# button_control_esp32.net
KiCad netlist of a schematic drawn in EAGLE
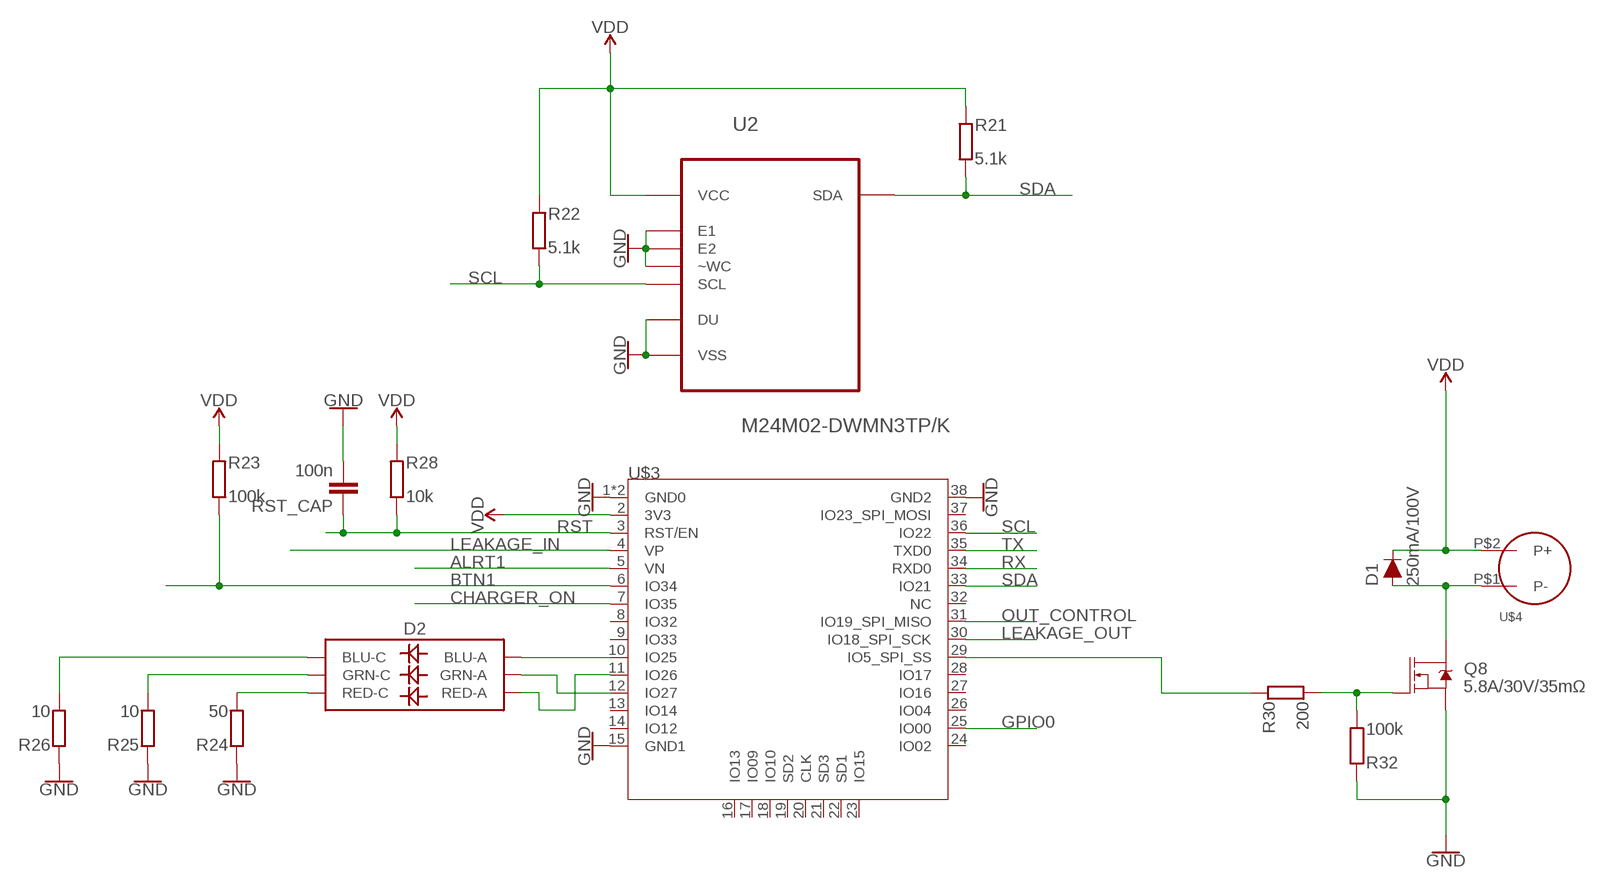
[diagram p0: schematic, sheet 1]
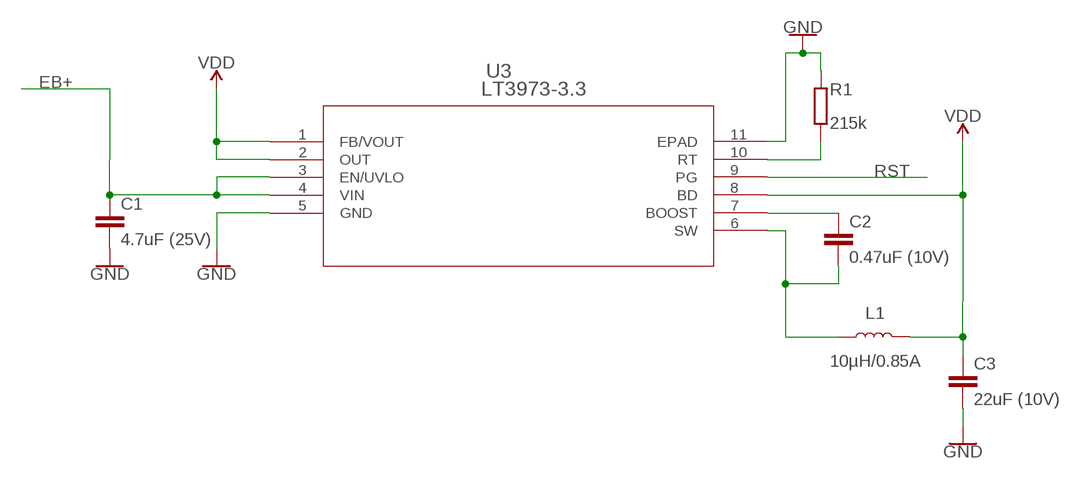
[diagram p1: schematic, sheet 2]
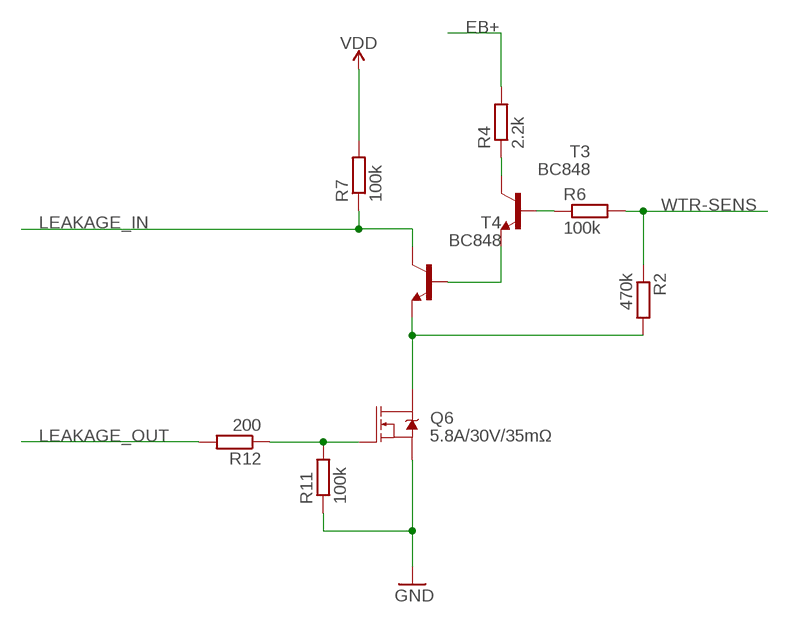
[diagram p2: schematic, sheet 3]
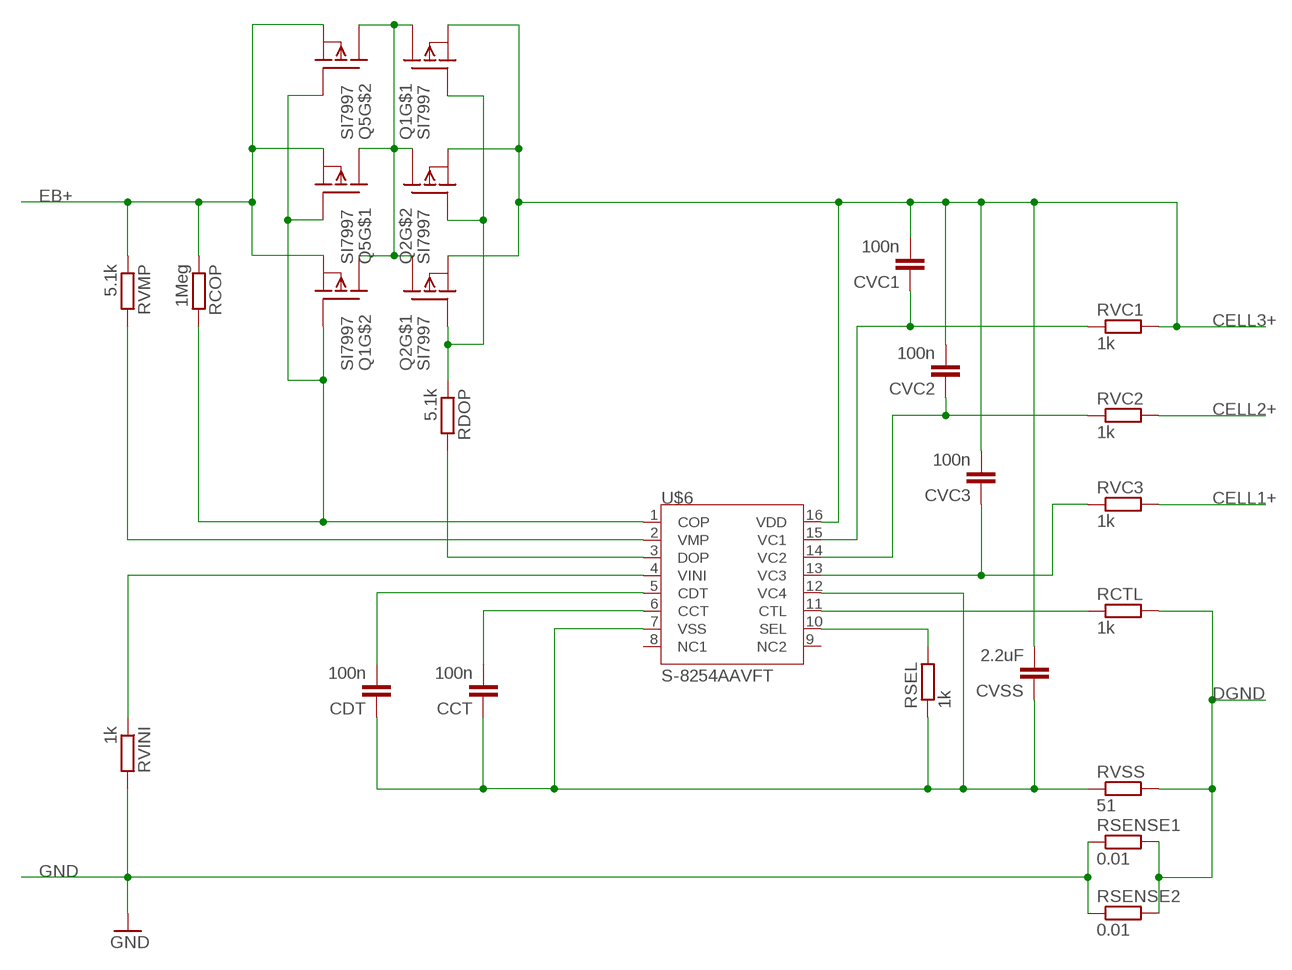
[diagram p3: schematic, sheet 4]
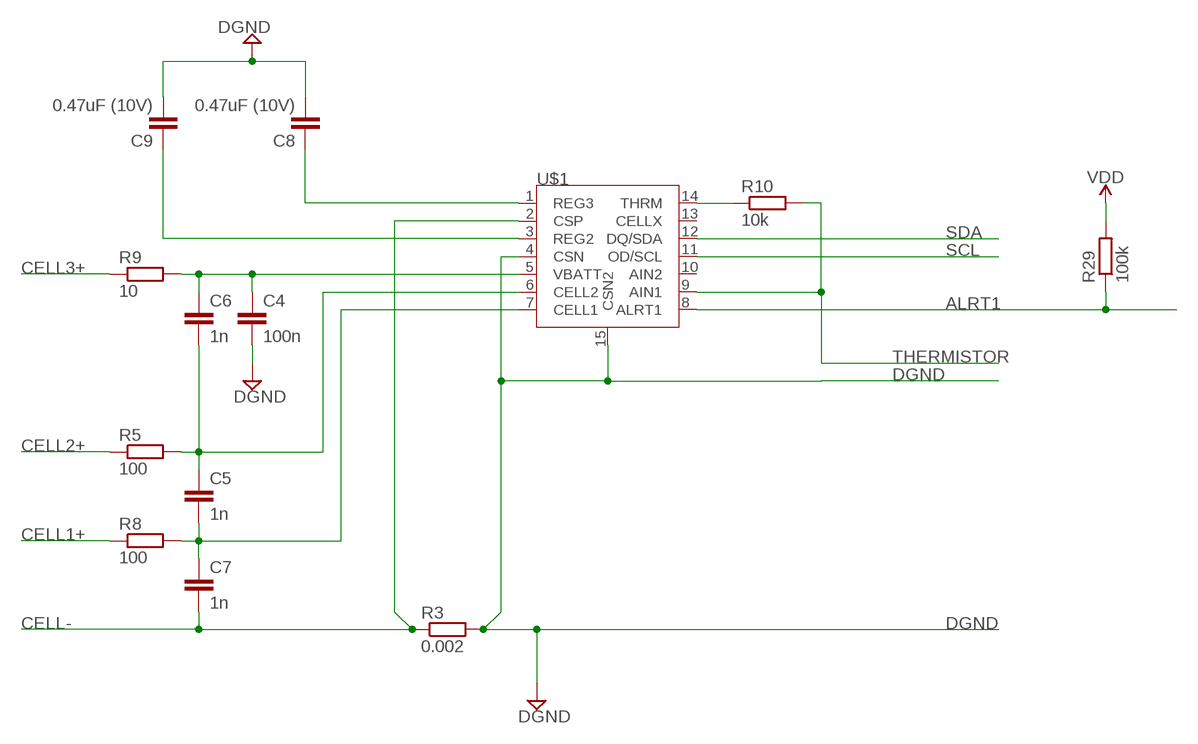
[diagram p4: schematic, sheet 5]
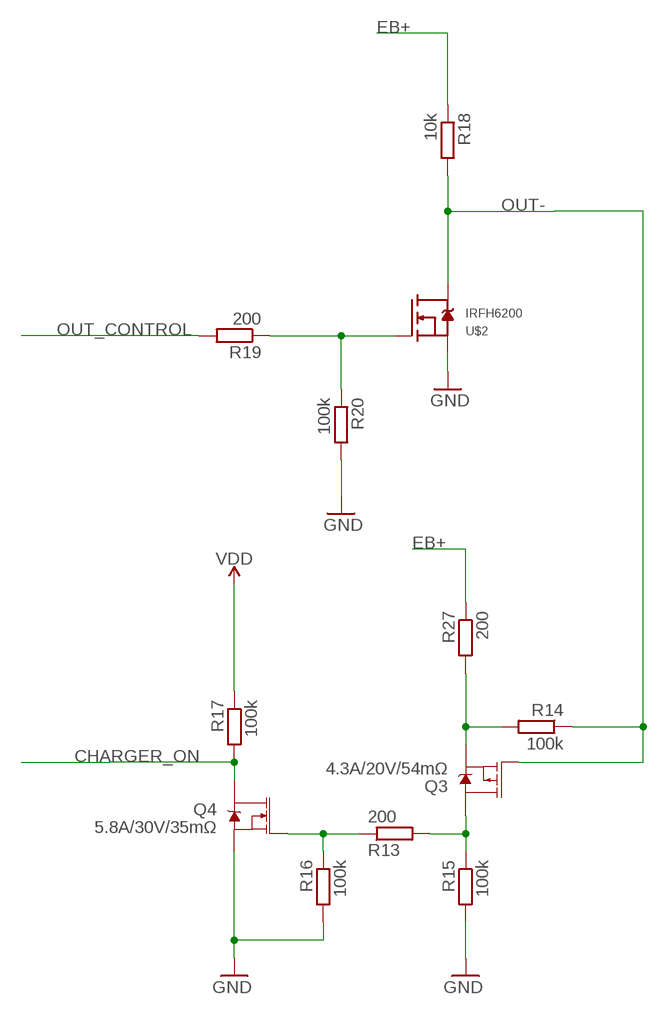
[diagram p5: schematic, sheet 6]
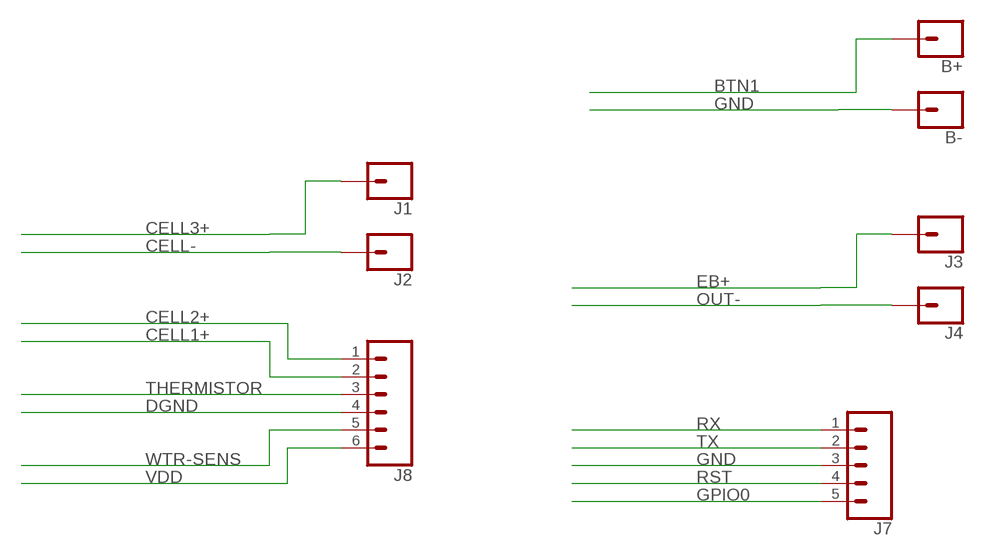
[diagram p6: schematic, sheet 7]

(export (version "E")
  (design (tool "Eeschema 10.0.6"))
  (components
    (comp (ref "CCT")
      (value "100n")
      (footprint "eagle-import:C0603")
      (libsource (lib "eagle-import") (part "C-EUC0603"))
    )
    (comp (ref "CDT")
      (value "100n")
      (footprint "eagle-import:C0603")
      (libsource (lib "eagle-import") (part "C-EUC0603"))
    )
    (comp (ref "CVC1")
      (value "100n")
      (footprint "eagle-import:C0603")
      (libsource (lib "eagle-import") (part "C-EUC0603"))
    )
    (comp (ref "CVC2")
      (value "100n")
      (footprint "eagle-import:C0603")
      (libsource (lib "eagle-import") (part "C-EUC0603"))
    )
    (comp (ref "CVC3")
      (value "100n")
      (footprint "eagle-import:C0603")
      (libsource (lib "eagle-import") (part "C-EUC0603"))
    )
    (comp (ref "CVSS")
      (value "2.2uF")
      (footprint "eagle-import:C0805")
      (libsource (lib "eagle-import") (part "C-EUC0805"))
    )
    (comp (ref "Q1")
      (value "SI7997")
      (footprint "eagle-import:POWERPAK")
      (libsource (lib "eagle-import") (part "SI7997"))
    )
    (comp (ref "Q2")
      (value "SI7997")
      (footprint "eagle-import:POWERPAK")
      (libsource (lib "eagle-import") (part "SI7997"))
    )
    (comp (ref "Q5")
      (value "SI7997")
      (footprint "eagle-import:POWERPAK")
      (libsource (lib "eagle-import") (part "SI7997"))
    )
    (comp (ref "RCOP")
      (value "1Meg")
      (footprint "eagle-import:R0603")
      (libsource (lib "eagle-import") (part "resistor_348_R-EU_R0603"))
    )
    (comp (ref "RCTL")
      (value "1k")
      (footprint "eagle-import:R0603")
      (libsource (lib "eagle-import") (part "resistor_348_R-EU_R0603"))
    )
    (comp (ref "RDOP")
      (value "5.1k")
      (footprint "eagle-import:R0603")
      (libsource (lib "eagle-import") (part "resistor_348_R-EU_R0603"))
    )
    (comp (ref "RSEL")
      (value "1k")
      (footprint "eagle-import:R0603")
      (libsource (lib "eagle-import") (part "resistor_348_R-EU_R0603"))
    )
    (comp (ref "RSENSE1")
      (value "0.01")
      (footprint "eagle-import:R2512")
      (libsource (lib "eagle-import") (part "resistor_348_R-EU_R2512"))
    )
    (comp (ref "RSENSE2")
      (value "0.01")
      (footprint "eagle-import:R2512")
      (libsource (lib "eagle-import") (part "resistor_348_R-EU_R2512"))
    )
    (comp (ref "RVC1")
      (value "1k")
      (footprint "eagle-import:R0603")
      (libsource (lib "eagle-import") (part "resistor_348_R-EU_R0603"))
    )
    (comp (ref "RVC2")
      (value "1k")
      (footprint "eagle-import:R0603")
      (libsource (lib "eagle-import") (part "resistor_348_R-EU_R0603"))
    )
    (comp (ref "RVC3")
      (value "1k")
      (footprint "eagle-import:R0603")
      (libsource (lib "eagle-import") (part "resistor_348_R-EU_R0603"))
    )
    (comp (ref "RVINI")
      (value "1k")
      (footprint "eagle-import:R0603")
      (libsource (lib "eagle-import") (part "resistor_348_R-EU_R0603"))
    )
    (comp (ref "RVMP")
      (value "5.1k")
      (footprint "eagle-import:R0603")
      (libsource (lib "eagle-import") (part "resistor_348_R-EU_R0603"))
    )
    (comp (ref "RVSS")
      (value "51")
      (footprint "eagle-import:R0603")
      (libsource (lib "eagle-import") (part "resistor_348_R-EU_R0603"))
    )
    (comp (ref "U$6")
      (value "S-8254AAVFT")
      (footprint "eagle-import:TSSOP-16")
      (libsource (lib "eagle-import") (part "S-8254A"))
    )
    (comp (ref "C4")
      (value "100n")
      (footprint "eagle-import:C0603")
      (libsource (lib "eagle-import") (part "C-EUC0603"))
    )
    (comp (ref "C5")
      (value "1n")
      (footprint "eagle-import:C0603")
      (libsource (lib "eagle-import") (part "C-EUC0603"))
    )
    (comp (ref "C6")
      (value "1n")
      (footprint "eagle-import:C0603")
      (libsource (lib "eagle-import") (part "C-EUC0603"))
    )
    (comp (ref "C7")
      (value "1n")
      (footprint "eagle-import:C0603")
      (libsource (lib "eagle-import") (part "C-EUC0603"))
    )
    (comp (ref "C8")
      (value "0.47uF (10V)")
      (footprint "eagle-import:C0603K")
      (libsource (lib "eagle-import") (part "C-EUC0603K"))
    )
    (comp (ref "C9")
      (value "0.47uF (10V)")
      (footprint "eagle-import:C0603K")
      (libsource (lib "eagle-import") (part "C-EUC0603K"))
    )
    (comp (ref "R3")
      (value "0.002")
      (footprint "eagle-import:R2512")
      (libsource (lib "eagle-import") (part "resistor_348_R-EU_R2512"))
    )
    (comp (ref "R5")
      (value "100")
      (footprint "eagle-import:R0805")
      (libsource (lib "eagle-import") (part "resistor_348_R-EU_R0805"))
    )
    (comp (ref "R8")
      (value "100")
      (footprint "eagle-import:R0805")
      (libsource (lib "eagle-import") (part "resistor_348_R-EU_R0805"))
    )
    (comp (ref "R9")
      (value "10")
      (footprint "eagle-import:R0603")
      (libsource (lib "eagle-import") (part "resistor_348_R-EU_R0603"))
    )
    (comp (ref "R10")
      (value "10k")
      (footprint "eagle-import:R0603")
      (libsource (lib "eagle-import") (part "resistor_348_R-EU_R0603"))
    )
    (comp (ref "R29")
      (value "100k")
      (footprint "eagle-import:R0603")
      (libsource (lib "eagle-import") (part "resistor_348_R-EU_R0603"))
    )
    (comp (ref "U$1")
      (value "MAX17205G")
      (footprint "eagle-import:SON40P300X300X80-15N230X170")
      (libsource (lib "eagle-import") (part "MAX17205G"))
    )
    (comp (ref "Q3")
      (value "4.3A/20V/54mΩ")
      (footprint "eagle-import:SOT23-3")
      (libsource (lib "eagle-import") (part "MOSFET_PCH-IRLML2244"))
    )
    (comp (ref "Q4")
      (value "5.8A/30V/35mΩ")
      (footprint "eagle-import:SOT23-3")
      (libsource (lib "eagle-import") (part "MOSFET-NCH-AO3404A"))
    )
    (comp (ref "R13")
      (value "200")
      (footprint "eagle-import:R0603")
      (libsource (lib "eagle-import") (part "R-EU_R0603"))
    )
    (comp (ref "R14")
      (value "100k")
      (footprint "eagle-import:R0603")
      (libsource (lib "eagle-import") (part "R-EU_R0603"))
    )
    (comp (ref "R15")
      (value "100k")
      (footprint "eagle-import:R0603")
      (libsource (lib "eagle-import") (part "R-EU_R0603"))
    )
    (comp (ref "R16")
      (value "100k")
      (footprint "eagle-import:R0603")
      (libsource (lib "eagle-import") (part "R-EU_R0603"))
    )
    (comp (ref "R17")
      (value "100k")
      (footprint "eagle-import:R0603")
      (libsource (lib "eagle-import") (part "R-EU_R0603"))
    )
    (comp (ref "R18")
      (value "10k")
      (footprint "eagle-import:R0603")
      (libsource (lib "eagle-import") (part "R-EU_R0603"))
    )
    (comp (ref "R19")
      (value "200")
      (footprint "eagle-import:R0603")
      (libsource (lib "eagle-import") (part "R-EU_R0603"))
    )
    (comp (ref "R20")
      (value "100k")
      (footprint "eagle-import:R0603")
      (libsource (lib "eagle-import") (part "R-EU_R0603"))
    )
    (comp (ref "R27")
      (value "200")
      (footprint "eagle-import:R0603")
      (libsource (lib "eagle-import") (part "R-EU_R0603"))
    )
    (comp (ref "U$2")
      (value "IRFH6200")
      (footprint "eagle-import:PQFN")
      (libsource (lib "eagle-import") (part "IRFH6200"))
    )
    (comp (ref "C1")
      (value "4.7uF (25V)")
      (footprint "eagle-import:C1206")
      (libsource (lib "eagle-import") (part "C-EUC1206"))
    )
    (comp (ref "C2")
      (value "0.47uF (10V)")
      (footprint "eagle-import:C0603K")
      (libsource (lib "eagle-import") (part "C-EUC0603K"))
    )
    (comp (ref "C3")
      (value "22uF (10V)")
      (footprint "eagle-import:C1206")
      (libsource (lib "eagle-import") (part "C-EUC1206"))
    )
    (comp (ref "L1")
      (value "10µH/0.85A")
      (footprint "eagle-import:INDUCTOR_4.7UH")
      (libsource (lib "eagle-import") (part "INDUCTOR-CDRH-4.7UH"))
    )
    (comp (ref "R1")
      (value "215k")
      (footprint "eagle-import:R0603")
      (libsource (lib "eagle-import") (part "resistor_348_R-EU_R0603"))
    )
    (comp (ref "U3")
      (value "LT3973-3.3")
      (footprint "eagle-import:DFN-10_DD")
      (fields
        (field (name "DIGI-KEY_PART_NUMBER") "LT3973IDD#PBF-ND")
        (field (name "MF") "Linear Technology")
        (field (name "MP") "LT3973IDD#PBF")
      )
      (libsource (lib "eagle-import") (part "LT3973IDDPBF"))
    )
    (comp (ref "B+")
      (value "CONN_01")
      (footprint "eagle-import:1X01")
      (libsource (lib "eagle-import") (part "CONN_01"))
    )
    (comp (ref "B-")
      (value "CONN_01")
      (footprint "eagle-import:1X01")
      (libsource (lib "eagle-import") (part "CONN_01"))
    )
    (comp (ref "J1")
      (value "CONN_01PTH_2MM")
      (footprint "eagle-import:1X01_2MM")
      (libsource (lib "eagle-import") (part "CONN_01PTH_2MM"))
    )
    (comp (ref "J2")
      (value "CONN_01PTH_2MM")
      (footprint "eagle-import:1X01_2MM")
      (libsource (lib "eagle-import") (part "CONN_01PTH_2MM"))
    )
    (comp (ref "J3")
      (value "CONN_01PTH_2MM")
      (footprint "eagle-import:1X01_2MM")
      (libsource (lib "eagle-import") (part "CONN_01PTH_2MM"))
    )
    (comp (ref "J4")
      (value "CONN_01PTH_2MM")
      (footprint "eagle-import:1X01_2MM")
      (libsource (lib "eagle-import") (part "CONN_01PTH_2MM"))
    )
    (comp (ref "J7")
      (value "CONN_051.27MM")
      (footprint "eagle-import:1X05_1.27MM")
      (libsource (lib "eagle-import") (part "CONN_051.27MM"))
    )
    (comp (ref "J8")
      (value "CONN_061.27MM")
      (footprint "eagle-import:1X06_1.27MM")
      (libsource (lib "eagle-import") (part "CONN_061.27MM"))
    )
    (comp (ref "D1")
      (value "250mA/100V")
      (footprint "eagle-import:SOD-323")
      (libsource (lib "eagle-import") (part "DIODE-BAS16J"))
    )
    (comp (ref "D2")
      (value "LED-RGBNO_IC")
      (footprint "eagle-import:LED-TRICOLOR-5050")
      (libsource (lib "eagle-import") (part "LED-RGBNO_IC"))
    )
    (comp (ref "Q8")
      (value "5.8A/30V/35mΩ")
      (footprint "eagle-import:SOT23-3")
      (libsource (lib "eagle-import") (part "MOSFET-NCH-AO3404A"))
    )
    (comp (ref "R21")
      (value "5.1k")
      (footprint "eagle-import:R0603")
      (libsource (lib "eagle-import") (part "resistor_348_R-EU_R0603"))
    )
    (comp (ref "R22")
      (value "5.1k")
      (footprint "eagle-import:R0603")
      (libsource (lib "eagle-import") (part "resistor_348_R-EU_R0603"))
    )
    (comp (ref "R23")
      (value "100k")
      (footprint "eagle-import:R0603")
      (libsource (lib "eagle-import") (part "resistor_348_R-EU_R0603"))
    )
    (comp (ref "R24")
      (value "50")
      (footprint "eagle-import:R0603")
      (libsource (lib "eagle-import") (part "resistor_348_R-EU_R0603"))
    )
    (comp (ref "R25")
      (value "10")
      (footprint "eagle-import:R0603")
      (libsource (lib "eagle-import") (part "resistor_348_R-EU_R0603"))
    )
    (comp (ref "R26")
      (value "10")
      (footprint "eagle-import:R0603")
      (libsource (lib "eagle-import") (part "resistor_348_R-EU_R0603"))
    )
    (comp (ref "R28")
      (value "10k")
      (footprint "eagle-import:R0603")
      (libsource (lib "eagle-import") (part "resistor_348_R-EU_R0603"))
    )
    (comp (ref "R30")
      (value "200")
      (footprint "eagle-import:R0603")
      (libsource (lib "eagle-import") (part "resistor_348_R-EU_R0603"))
    )
    (comp (ref "R32")
      (value "100k")
      (footprint "eagle-import:R0603")
      (libsource (lib "eagle-import") (part "resistor_348_R-EU_R0603"))
    )
    (comp (ref "RST_CAP")
      (value "100n")
      (footprint "eagle-import:C0603")
      (libsource (lib "eagle-import") (part "C-EUC0603"))
    )
    (comp (ref "U$3")
      (value "ESP32")
      (footprint "eagle-import:TTGO_ESP32")
      (libsource (lib "eagle-import") (part "ESP32"))
    )
    (comp (ref "U$4")
      (value "VIBRO")
      (footprint "eagle-import:VIBRO")
      (libsource (lib "eagle-import") (part "VIBRO"))
    )
    (comp (ref "U2")
      (value "M24M02-DWMN3TP/K")
      (footprint "eagle-import:SOIC127P600X175-8N")
      (fields (field (name "DIGI-KEY_PART_NUMBER") "497-16238-1-ND") (field (name "MF") "STMicroelectronics"))
      (libsource (lib "eagle-import") (part "M24M02-DWMN3TP/K"))
    )
    (comp (ref "Q6")
      (value "5.8A/30V/35mΩ")
      (footprint "eagle-import:SOT23-3")
      (libsource (lib "eagle-import") (part "MOSFET-NCH-AO3404A"))
    )
    (comp (ref "R2")
      (value "470k")
      (footprint "eagle-import:R0603")
      (libsource (lib "eagle-import") (part "R-EU_R0603"))
    )
    (comp (ref "R4")
      (value "2.2k")
      (footprint "eagle-import:R0603")
      (libsource (lib "eagle-import") (part "R-EU_R0603"))
    )
    (comp (ref "R6")
      (value "100k")
      (footprint "eagle-import:R0603")
      (libsource (lib "eagle-import") (part "R-EU_R0603"))
    )
    (comp (ref "R7")
      (value "100k")
      (footprint "eagle-import:R0603")
      (libsource (lib "eagle-import") (part "R-EU_R0603"))
    )
    (comp (ref "R11")
      (value "100k")
      (footprint "eagle-import:R0603")
      (libsource (lib "eagle-import") (part "R-EU_R0603"))
    )
    (comp (ref "R12")
      (value "200")
      (footprint "eagle-import:R0603")
      (libsource (lib "eagle-import") (part "R-EU_R0603"))
    )
    (comp (ref "T3")
      (value "BC848")
      (footprint "eagle-import:SOT23")
      (libsource (lib "eagle-import") (part "BC848"))
    )
    (comp (ref "T4")
      (value "BC848")
      (footprint "eagle-import:SOT23")
      (fields (field (name "SPICEPREFIX") "Q"))
      (libsource (lib "eagle-import") (part "BC848"))
    )
  )
  (nets
    (net (code "1") (name "ALRT1") (class "Default")
      (node (ref "R29") (pin "1") (pinfunction "1_1") (pintype "passive"))
      (node (ref "U$1") (pin "8") (pinfunction "ALRT1_8") (pintype "bidirectional"))
      (node (ref "U$3") (pin "5") (pinfunction "VN_5") (pintype "bidirectional"))
    )
    (net (code "2") (name "BTN1") (class "Default")
      (node (ref "B+") (pin "1") (pinfunction "1_1") (pintype "passive"))
      (node (ref "R23") (pin "1") (pinfunction "1_1") (pintype "passive"))
      (node (ref "U$3") (pin "6") (pinfunction "IO34_6") (pintype "bidirectional"))
    )
    (net (code "3") (name "CELL-") (class "Default")
      (node (ref "C7") (pin "2") (pinfunction "2_2") (pintype "passive"))
      (node (ref "J2") (pin "1") (pinfunction "1_1") (pintype "passive"))
      (node (ref "R3") (pin "1") (pinfunction "1_1") (pintype "passive"))
      (node (ref "U$1") (pin "2") (pinfunction "CSP_2") (pintype "bidirectional"))
    )
    (net (code "4") (name "CELL1+") (class "Default")
      (node (ref "J8") (pin "2") (pinfunction "2_2") (pintype "passive"))
      (node (ref "R8") (pin "1") (pinfunction "1_1") (pintype "passive"))
      (node (ref "RVC3") (pin "2") (pinfunction "2_2") (pintype "passive"))
    )
    (net (code "5") (name "CELL2+") (class "Default")
      (node (ref "J8") (pin "1") (pinfunction "1_1") (pintype "passive"))
      (node (ref "R5") (pin "1") (pinfunction "1_1") (pintype "passive"))
      (node (ref "RVC2") (pin "2") (pinfunction "2_2") (pintype "passive"))
    )
    (net (code "6") (name "CELL3+") (class "Default")
      (node (ref "CVC1") (pin "2") (pinfunction "2_2") (pintype "passive"))
      (node (ref "CVC2") (pin "2") (pinfunction "2_2") (pintype "passive"))
      (node (ref "CVC3") (pin "2") (pinfunction "2_2") (pintype "passive"))
      (node (ref "CVSS") (pin "2") (pinfunction "2_2") (pintype "passive"))
      (node (ref "J1") (pin "1") (pinfunction "1_1") (pintype "passive"))
      (node (ref "Q1") (pin "1") (pinfunction "S_1") (pintype "passive"))
      (node (ref "Q2") (pin "1") (pinfunction "S_1") (pintype "passive"))
      (node (ref "Q2") (pin "3") (pinfunction "S_3") (pintype "passive"))
      (node (ref "R9") (pin "1") (pinfunction "1_1") (pintype "passive"))
      (node (ref "RVC1") (pin "2") (pinfunction "2_2") (pintype "passive"))
      (node (ref "U$6") (pin "16") (pinfunction "VDD_16") (pintype "bidirectional"))
    )
    (net (code "7") (name "CHARGER_ON") (class "Default")
      (node (ref "Q4") (pin "3") (pinfunction "D_3") (pintype "bidirectional"))
      (node (ref "R17") (pin "2") (pinfunction "2_2") (pintype "passive"))
      (node (ref "U$3") (pin "7") (pinfunction "IO35_7") (pintype "bidirectional"))
    )
    (net (code "8") (name "DGND") (class "Default")
      (node (ref "C4") (pin "2") (pinfunction "2_2") (pintype "passive"))
      (node (ref "C8") (pin "2") (pinfunction "2_2") (pintype "passive"))
      (node (ref "C9") (pin "2") (pinfunction "2_2") (pintype "passive"))
      (node (ref "J8") (pin "4") (pinfunction "4_4") (pintype "passive"))
      (node (ref "R3") (pin "2") (pinfunction "2_2") (pintype "passive"))
      (node (ref "RCTL") (pin "2") (pinfunction "2_2") (pintype "passive"))
      (node (ref "RSENSE1") (pin "2") (pinfunction "2_2") (pintype "passive"))
      (node (ref "RSENSE2") (pin "2") (pinfunction "2_2") (pintype "passive"))
      (node (ref "RVSS") (pin "2") (pinfunction "2_2") (pintype "passive"))
      (node (ref "U$1") (pin "15") (pinfunction "CSN2_15") (pintype "bidirectional"))
      (node (ref "U$1") (pin "4") (pinfunction "CSN_4") (pintype "bidirectional"))
    )
    (net (code "9") (name "EB+") (class "Default")
      (node (ref "C1") (pin "1") (pinfunction "1_1") (pintype "passive"))
      (node (ref "J3") (pin "1") (pinfunction "1_1") (pintype "passive"))
      (node (ref "Q1") (pin "3") (pinfunction "S_3") (pintype "passive"))
      (node (ref "Q5") (pin "1") (pinfunction "S_1") (pintype "passive"))
      (node (ref "Q5") (pin "3") (pinfunction "S_3") (pintype "passive"))
      (node (ref "R18") (pin "1") (pinfunction "1_1") (pintype "passive"))
      (node (ref "R27") (pin "1") (pinfunction "1_1") (pintype "passive"))
      (node (ref "R4") (pin "2") (pinfunction "2_2") (pintype "passive"))
      (node (ref "RCOP") (pin "1") (pinfunction "1_1") (pintype "passive"))
      (node (ref "RVMP") (pin "1") (pinfunction "1_1") (pintype "passive"))
      (node (ref "U3") (pin "3") (pinfunction "EN/UVLO_3") (pintype "bidirectional"))
      (node (ref "U3") (pin "4") (pinfunction "VIN_4") (pintype "input"))
    )
    (net (code "10") (name "GND") (class "Default")
      (node (ref "B-") (pin "1") (pinfunction "1_1") (pintype "passive"))
      (node (ref "C1") (pin "2") (pinfunction "2_2") (pintype "passive"))
      (node (ref "C3") (pin "2") (pinfunction "2_2") (pintype "passive"))
      (node (ref "J7") (pin "3") (pinfunction "3_3") (pintype "passive"))
      (node (ref "Q4") (pin "2") (pinfunction "S_2") (pintype "bidirectional"))
      (node (ref "Q6") (pin "2") (pinfunction "S_2") (pintype "bidirectional"))
      (node (ref "Q8") (pin "2") (pinfunction "S_2") (pintype "bidirectional"))
      (node (ref "R1") (pin "2") (pinfunction "2_2") (pintype "passive"))
      (node (ref "R11") (pin "1") (pinfunction "1_1") (pintype "passive"))
      (node (ref "R15") (pin "2") (pinfunction "2_2") (pintype "passive"))
      (node (ref "R16") (pin "2") (pinfunction "2_2") (pintype "passive"))
      (node (ref "R20") (pin "2") (pinfunction "2_2") (pintype "passive"))
      (node (ref "R24") (pin "2") (pinfunction "2_2") (pintype "passive"))
      (node (ref "R25") (pin "2") (pinfunction "2_2") (pintype "passive"))
      (node (ref "R26") (pin "2") (pinfunction "2_2") (pintype "passive"))
      (node (ref "R32") (pin "2") (pinfunction "2_2") (pintype "passive"))
      (node (ref "RSENSE1") (pin "1") (pinfunction "1_1") (pintype "passive"))
      (node (ref "RSENSE2") (pin "1") (pinfunction "1_1") (pintype "passive"))
      (node (ref "RST_CAP") (pin "2") (pinfunction "2_2") (pintype "passive"))
      (node (ref "RVINI") (pin "2") (pinfunction "2_2") (pintype "passive"))
      (node (ref "U$2") (pin "1") (pinfunction "S_1") (pintype "power_in"))
      (node (ref "U$2") (pin "2") (pinfunction "S_2") (pintype "power_in"))
      (node (ref "U$2") (pin "3") (pinfunction "S_3") (pintype "power_in"))
      (node (ref "U$3") (pin "1") (pinfunction "GND0_1") (pintype "bidirectional"))
      (node (ref "U$3") (pin "15") (pinfunction "GND1_15") (pintype "bidirectional"))
      (node (ref "U$3") (pin "38") (pinfunction "GND2_38") (pintype "bidirectional"))
      (node (ref "U$3") (pin "P$1") (pinfunction "GND0_P$1") (pintype "bidirectional"))
      (node (ref "U2") (pin "1") (pinfunction "DU_1") (pintype "input"))
      (node (ref "U2") (pin "2") (pinfunction "E1_2") (pintype "input"))
      (node (ref "U2") (pin "3") (pinfunction "E2_3") (pintype "input"))
      (node (ref "U2") (pin "4") (pinfunction "VSS_4") (pintype "power_in"))
      (node (ref "U2") (pin "7") (pinfunction "~{WC}_7") (pintype "input"))
      (node (ref "U3") (pin "11") (pinfunction "EPAD_11") (pintype "passive"))
      (node (ref "U3") (pin "5") (pinfunction "GND_5") (pintype "power_in"))
    )
    (net (code "11") (name "GPIO0") (class "Default")
      (node (ref "J7") (pin "5") (pinfunction "5_5") (pintype "passive"))
      (node (ref "U$3") (pin "25") (pinfunction "IO00_25") (pintype "bidirectional"))
    )
    (net (code "12") (name "LEAKAGE_IN") (class "Default")
      (node (ref "R7") (pin "1") (pinfunction "1_1") (pintype "passive"))
      (node (ref "T4") (pin "3") (pinfunction "C_3") (pintype "passive"))
      (node (ref "U$3") (pin "4") (pinfunction "VP_4") (pintype "bidirectional"))
    )
    (net (code "13") (name "LEAKAGE_OUT") (class "Default")
      (node (ref "R12") (pin "2") (pinfunction "2_2") (pintype "passive"))
      (node (ref "U$3") (pin "30") (pinfunction "IO18_SPI_SCK_30") (pintype "bidirectional"))
    )
    (net (code "14") (name "Net-(D2-BLU-A)") (class "Default")
      (node (ref "D2") (pin "3") (pinfunction "BLU-A_3") (pintype "bidirectional"))
      (node (ref "U$3") (pin "10") (pinfunction "IO25_10") (pintype "bidirectional"))
    )
    (net (code "15") (name "Net-(D2-BLU-C)") (class "Default")
      (node (ref "D2") (pin "4") (pinfunction "BLU-C_4") (pintype "bidirectional"))
      (node (ref "R26") (pin "1") (pinfunction "1_1") (pintype "passive"))
    )
    (net (code "16") (name "Net-(D2-GRN-A)") (class "Default")
      (node (ref "D2") (pin "1") (pinfunction "GRN-A_1") (pintype "bidirectional"))
      (node (ref "U$3") (pin "12") (pinfunction "IO27_12") (pintype "bidirectional"))
    )
    (net (code "17") (name "Net-(D2-GRN-C)") (class "Default")
      (node (ref "D2") (pin "6") (pinfunction "GRN-C_6") (pintype "bidirectional"))
      (node (ref "R25") (pin "1") (pinfunction "1_1") (pintype "passive"))
    )
    (net (code "18") (name "Net-(D2-RED-A)") (class "Default")
      (node (ref "D2") (pin "2") (pinfunction "RED-A_2") (pintype "bidirectional"))
      (node (ref "U$3") (pin "11") (pinfunction "IO26_11") (pintype "bidirectional"))
    )
    (net (code "19") (name "Net-(D2-RED-C)") (class "Default")
      (node (ref "D2") (pin "5") (pinfunction "RED-C_5") (pintype "bidirectional"))
      (node (ref "R24") (pin "1") (pinfunction "1_1") (pintype "passive"))
    )
    (net (code "20") (name "Net-(L1-1)") (class "Default")
      (node (ref "C2") (pin "2") (pinfunction "2_2") (pintype "passive"))
      (node (ref "L1") (pin "P$1") (pinfunction "1_P$1") (pintype "passive"))
      (node (ref "U3") (pin "6") (pinfunction "SW_6") (pintype "output"))
    )
    (net (code "21") (name "Net-(Q1A-D-Pad7)") (class "Default")
      (node (ref "Q1") (pin "5") (pinfunction "D_5") (pintype "passive"))
      (node (ref "Q1") (pin "5_6") (pinfunction "D_5_6") (pintype "passive"))
      (node (ref "Q1") (pin "6") (pinfunction "D_6") (pintype "passive"))
      (node (ref "Q1") (pin "7") (pinfunction "D_7") (pintype "passive"))
      (node (ref "Q1") (pin "7_8") (pinfunction "D_7_8") (pintype "passive"))
      (node (ref "Q1") (pin "8") (pinfunction "D_8") (pintype "passive"))
      (node (ref "Q2") (pin "5") (pinfunction "D_5") (pintype "passive"))
      (node (ref "Q2") (pin "5_6") (pinfunction "D_5_6") (pintype "passive"))
      (node (ref "Q2") (pin "6") (pinfunction "D_6") (pintype "passive"))
      (node (ref "Q2") (pin "7") (pinfunction "D_7") (pintype "passive"))
      (node (ref "Q2") (pin "7_8") (pinfunction "D_7_8") (pintype "passive"))
      (node (ref "Q2") (pin "8") (pinfunction "D_8") (pintype "passive"))
      (node (ref "Q5") (pin "5") (pinfunction "D_5") (pintype "passive"))
      (node (ref "Q5") (pin "5_6") (pinfunction "D_5_6") (pintype "passive"))
      (node (ref "Q5") (pin "6") (pinfunction "D_6") (pintype "passive"))
      (node (ref "Q5") (pin "7") (pinfunction "D_7") (pintype "passive"))
      (node (ref "Q5") (pin "7_8") (pinfunction "D_7_8") (pintype "passive"))
      (node (ref "Q5") (pin "8") (pinfunction "D_8") (pintype "passive"))
    )
    (net (code "22") (name "Net-(Q1A-G)") (class "Default")
      (node (ref "Q1") (pin "2") (pinfunction "G_2") (pintype "passive"))
      (node (ref "Q2") (pin "2") (pinfunction "G_2") (pintype "passive"))
      (node (ref "Q2") (pin "4") (pinfunction "G_4") (pintype "passive"))
      (node (ref "RDOP") (pin "1") (pinfunction "1_1") (pintype "passive"))
    )
    (net (code "23") (name "Net-(Q1B-G)") (class "Default")
      (node (ref "Q1") (pin "4") (pinfunction "G_4") (pintype "passive"))
      (node (ref "Q5") (pin "2") (pinfunction "G_2") (pintype "passive"))
      (node (ref "Q5") (pin "4") (pinfunction "G_4") (pintype "passive"))
      (node (ref "RCOP") (pin "2") (pinfunction "2_2") (pintype "passive"))
      (node (ref "U$6") (pin "1") (pinfunction "COP_1") (pintype "bidirectional"))
    )
    (net (code "24") (name "Net-(Q3-D)") (class "Default")
      (node (ref "Q3") (pin "3") (pinfunction "D_3") (pintype "bidirectional"))
      (node (ref "R13") (pin "2") (pinfunction "2_2") (pintype "passive"))
      (node (ref "R15") (pin "1") (pinfunction "1_1") (pintype "passive"))
    )
    (net (code "25") (name "Net-(Q3-S)") (class "Default")
      (node (ref "Q3") (pin "2") (pinfunction "S_2") (pintype "bidirectional"))
      (node (ref "R14") (pin "2") (pinfunction "2_2") (pintype "passive"))
      (node (ref "R27") (pin "2") (pinfunction "2_2") (pintype "passive"))
    )
    (net (code "26") (name "Net-(Q4-G)") (class "Default")
      (node (ref "Q4") (pin "1") (pinfunction "G_1") (pintype "bidirectional"))
      (node (ref "R13") (pin "1") (pinfunction "1_1") (pintype "passive"))
      (node (ref "R16") (pin "1") (pinfunction "1_1") (pintype "passive"))
    )
    (net (code "27") (name "Net-(Q6-D)") (class "Default")
      (node (ref "Q6") (pin "3") (pinfunction "D_3") (pintype "bidirectional"))
      (node (ref "R2") (pin "2") (pinfunction "2_2") (pintype "passive"))
      (node (ref "T4") (pin "2") (pinfunction "E_2") (pintype "passive"))
    )
    (net (code "28") (name "Net-(Q6-G)") (class "Default")
      (node (ref "Q6") (pin "1") (pinfunction "G_1") (pintype "bidirectional"))
      (node (ref "R11") (pin "2") (pinfunction "2_2") (pintype "passive"))
      (node (ref "R12") (pin "1") (pinfunction "1_1") (pintype "passive"))
    )
    (net (code "29") (name "Net-(Q8-D)") (class "Default")
      (node (ref "D1") (pin "A") (pinfunction "A_A") (pintype "passive"))
      (node (ref "Q8") (pin "3") (pinfunction "D_3") (pintype "bidirectional"))
      (node (ref "U$4") (pin "P$1") (pinfunction "P-_P$1") (pintype "power_in"))
    )
    (net (code "30") (name "Net-(Q8-G)") (class "Default")
      (node (ref "Q8") (pin "1") (pinfunction "G_1") (pintype "bidirectional"))
      (node (ref "R30") (pin "1") (pinfunction "1_1") (pintype "passive"))
      (node (ref "R32") (pin "1") (pinfunction "1_1") (pintype "passive"))
    )
    (net (code "31") (name "Net-(T3-B)") (class "Default")
      (node (ref "R6") (pin "1") (pinfunction "1_1") (pintype "passive"))
      (node (ref "T3") (pin "1") (pinfunction "B_1") (pintype "passive"))
    )
    (net (code "32") (name "Net-(T3-C)") (class "Default")
      (node (ref "R4") (pin "1") (pinfunction "1_1") (pintype "passive"))
      (node (ref "T3") (pin "3") (pinfunction "C_3") (pintype "passive"))
    )
    (net (code "33") (name "Net-(T3-E)") (class "Default")
      (node (ref "T3") (pin "2") (pinfunction "E_2") (pintype "passive"))
      (node (ref "T4") (pin "1") (pinfunction "B_1") (pintype "passive"))
    )
    (net (code "34") (name "Net-(U$1-CELL1)") (class "Default")
      (node (ref "C5") (pin "2") (pinfunction "2_2") (pintype "passive"))
      (node (ref "C7") (pin "1") (pinfunction "1_1") (pintype "passive"))
      (node (ref "R8") (pin "2") (pinfunction "2_2") (pintype "passive"))
      (node (ref "U$1") (pin "7") (pinfunction "CELL1_7") (pintype "bidirectional"))
    )
    (net (code "35") (name "Net-(U$1-CELL2)") (class "Default")
      (node (ref "C5") (pin "1") (pinfunction "1_1") (pintype "passive"))
      (node (ref "C6") (pin "2") (pinfunction "2_2") (pintype "passive"))
      (node (ref "R5") (pin "2") (pinfunction "2_2") (pintype "passive"))
      (node (ref "U$1") (pin "6") (pinfunction "CELL2_6") (pintype "bidirectional"))
    )
    (net (code "36") (name "Net-(U$1-REG2)") (class "Default")
      (node (ref "C9") (pin "1") (pinfunction "1_1") (pintype "passive"))
      (node (ref "U$1") (pin "3") (pinfunction "REG2_3") (pintype "bidirectional"))
    )
    (net (code "37") (name "Net-(U$1-REG3)") (class "Default")
      (node (ref "C8") (pin "1") (pinfunction "1_1") (pintype "passive"))
      (node (ref "U$1") (pin "1") (pinfunction "REG3_1") (pintype "bidirectional"))
    )
    (net (code "38") (name "Net-(U$1-THRM)") (class "Default")
      (node (ref "R10") (pin "1") (pinfunction "1_1") (pintype "passive"))
      (node (ref "U$1") (pin "14") (pinfunction "THRM_14") (pintype "bidirectional"))
    )
    (net (code "39") (name "Net-(U$1-VBATT)") (class "Default")
      (node (ref "C4") (pin "1") (pinfunction "1_1") (pintype "passive"))
      (node (ref "C6") (pin "1") (pinfunction "1_1") (pintype "passive"))
      (node (ref "R9") (pin "2") (pinfunction "2_2") (pintype "passive"))
      (node (ref "U$1") (pin "5") (pinfunction "VBATT_5") (pintype "bidirectional"))
    )
    (net (code "40") (name "Net-(U$2-G)") (class "Default")
      (node (ref "R19") (pin "1") (pinfunction "1_1") (pintype "passive"))
      (node (ref "R20") (pin "1") (pinfunction "1_1") (pintype "passive"))
      (node (ref "U$2") (pin "4") (pinfunction "G_4") (pintype "bidirectional"))
    )
    (net (code "41") (name "Net-(U$3-IO5_SPI_SS)") (class "Default")
      (node (ref "R30") (pin "2") (pinfunction "2_2") (pintype "passive"))
      (node (ref "U$3") (pin "29") (pinfunction "IO5_SPI_SS_29") (pintype "bidirectional"))
    )
    (net (code "42") (name "Net-(U$6-CCT)") (class "Default")
      (node (ref "CCT") (pin "2") (pinfunction "2_2") (pintype "passive"))
      (node (ref "U$6") (pin "6") (pinfunction "CCT_6") (pintype "bidirectional"))
    )
    (net (code "43") (name "Net-(U$6-CDT)") (class "Default")
      (node (ref "CDT") (pin "2") (pinfunction "2_2") (pintype "passive"))
      (node (ref "U$6") (pin "5") (pinfunction "CDT_5") (pintype "bidirectional"))
    )
    (net (code "44") (name "Net-(U$6-CTL)") (class "Default")
      (node (ref "RCTL") (pin "1") (pinfunction "1_1") (pintype "passive"))
      (node (ref "U$6") (pin "11") (pinfunction "CTL_11") (pintype "bidirectional"))
    )
    (net (code "45") (name "Net-(U$6-DOP)") (class "Default")
      (node (ref "RDOP") (pin "2") (pinfunction "2_2") (pintype "passive"))
      (node (ref "U$6") (pin "3") (pinfunction "DOP_3") (pintype "bidirectional"))
    )
    (net (code "46") (name "Net-(U$6-SEL)") (class "Default")
      (node (ref "RSEL") (pin "2") (pinfunction "2_2") (pintype "passive"))
      (node (ref "U$6") (pin "10") (pinfunction "SEL_10") (pintype "bidirectional"))
    )
    (net (code "47") (name "Net-(U$6-VC1)") (class "Default")
      (node (ref "CVC1") (pin "1") (pinfunction "1_1") (pintype "passive"))
      (node (ref "RVC1") (pin "1") (pinfunction "1_1") (pintype "passive"))
      (node (ref "U$6") (pin "15") (pinfunction "VC1_15") (pintype "bidirectional"))
    )
    (net (code "48") (name "Net-(U$6-VC2)") (class "Default")
      (node (ref "CVC2") (pin "1") (pinfunction "1_1") (pintype "passive"))
      (node (ref "RVC2") (pin "1") (pinfunction "1_1") (pintype "passive"))
      (node (ref "U$6") (pin "14") (pinfunction "VC2_14") (pintype "bidirectional"))
    )
    (net (code "49") (name "Net-(U$6-VC3)") (class "Default")
      (node (ref "CVC3") (pin "1") (pinfunction "1_1") (pintype "passive"))
      (node (ref "RVC3") (pin "1") (pinfunction "1_1") (pintype "passive"))
      (node (ref "U$6") (pin "13") (pinfunction "VC3_13") (pintype "bidirectional"))
    )
    (net (code "50") (name "Net-(U$6-VC4)") (class "Default")
      (node (ref "CCT") (pin "1") (pinfunction "1_1") (pintype "passive"))
      (node (ref "CDT") (pin "1") (pinfunction "1_1") (pintype "passive"))
      (node (ref "CVSS") (pin "1") (pinfunction "1_1") (pintype "passive"))
      (node (ref "RSEL") (pin "1") (pinfunction "1_1") (pintype "passive"))
      (node (ref "RVSS") (pin "1") (pinfunction "1_1") (pintype "passive"))
      (node (ref "U$6") (pin "12") (pinfunction "VC4_12") (pintype "bidirectional"))
      (node (ref "U$6") (pin "7") (pinfunction "VSS_7") (pintype "bidirectional"))
    )
    (net (code "51") (name "Net-(U$6-VINI)") (class "Default")
      (node (ref "RVINI") (pin "1") (pinfunction "1_1") (pintype "passive"))
      (node (ref "U$6") (pin "4") (pinfunction "VINI_4") (pintype "bidirectional"))
    )
    (net (code "52") (name "Net-(U$6-VMP)") (class "Default")
      (node (ref "RVMP") (pin "2") (pinfunction "2_2") (pintype "passive"))
      (node (ref "U$6") (pin "2") (pinfunction "VMP_2") (pintype "bidirectional"))
    )
    (net (code "53") (name "Net-(U3-BOOST)") (class "Default")
      (node (ref "C2") (pin "1") (pinfunction "1_1") (pintype "passive"))
      (node (ref "U3") (pin "7") (pinfunction "BOOST_7") (pintype "input"))
    )
    (net (code "54") (name "Net-(U3-RT)") (class "Default")
      (node (ref "R1") (pin "1") (pinfunction "1_1") (pintype "passive"))
      (node (ref "U3") (pin "10") (pinfunction "RT_10") (pintype "passive"))
    )
    (net (code "55") (name "OUT-") (class "Default")
      (node (ref "J4") (pin "1") (pinfunction "1_1") (pintype "passive"))
      (node (ref "Q3") (pin "1") (pinfunction "G_1") (pintype "bidirectional"))
      (node (ref "R14") (pin "1") (pinfunction "1_1") (pintype "passive"))
      (node (ref "R18") (pin "2") (pinfunction "2_2") (pintype "passive"))
      (node (ref "U$2") (pin "5") (pinfunction "D_5") (pintype "power_in"))
      (node (ref "U$2") (pin "6") (pinfunction "D_6") (pintype "power_in"))
      (node (ref "U$2") (pin "7") (pinfunction "D_7") (pintype "power_in"))
      (node (ref "U$2") (pin "8") (pinfunction "D_8") (pintype "power_in"))
      (node (ref "U$2") (pin "9") (pinfunction "D_9") (pintype "power_in"))
    )
    (net (code "56") (name "OUT_CONTROL") (class "Default")
      (node (ref "R19") (pin "2") (pinfunction "2_2") (pintype "passive"))
      (node (ref "U$3") (pin "31") (pinfunction "IO19_SPI_MISO_31") (pintype "bidirectional"))
    )
    (net (code "57") (name "RST") (class "Default")
      (node (ref "J7") (pin "4") (pinfunction "4_4") (pintype "passive"))
      (node (ref "R28") (pin "1") (pinfunction "1_1") (pintype "passive"))
      (node (ref "RST_CAP") (pin "1") (pinfunction "1_1") (pintype "passive"))
      (node (ref "U$3") (pin "3") (pinfunction "RST/EN_3") (pintype "bidirectional"))
      (node (ref "U3") (pin "9") (pinfunction "PG_9") (pintype "output"))
    )
    (net (code "58") (name "RX") (class "Default")
      (node (ref "J7") (pin "1") (pinfunction "1_1") (pintype "passive"))
      (node (ref "U$3") (pin "34") (pinfunction "RXD0_34") (pintype "bidirectional"))
    )
    (net (code "59") (name "SCL") (class "Default")
      (node (ref "R22") (pin "1") (pinfunction "1_1") (pintype "passive"))
      (node (ref "U$1") (pin "11") (pinfunction "OD/SCL_11") (pintype "bidirectional"))
      (node (ref "U$3") (pin "36") (pinfunction "IO22_36") (pintype "bidirectional"))
      (node (ref "U2") (pin "6") (pinfunction "SCL_6") (pintype "input"))
    )
    (net (code "60") (name "SDA") (class "Default")
      (node (ref "R21") (pin "1") (pinfunction "1_1") (pintype "passive"))
      (node (ref "U$1") (pin "12") (pinfunction "DQ/SDA_12") (pintype "bidirectional"))
      (node (ref "U$3") (pin "33") (pinfunction "IO21_33") (pintype "bidirectional"))
      (node (ref "U2") (pin "5") (pinfunction "SDA_5") (pintype "output"))
    )
    (net (code "61") (name "THERMISTOR") (class "Default")
      (node (ref "J8") (pin "3") (pinfunction "3_3") (pintype "passive"))
      (node (ref "R10") (pin "2") (pinfunction "2_2") (pintype "passive"))
      (node (ref "U$1") (pin "9") (pinfunction "AIN1_9") (pintype "bidirectional"))
    )
    (net (code "62") (name "TX") (class "Default")
      (node (ref "J7") (pin "2") (pinfunction "2_2") (pintype "passive"))
      (node (ref "U$3") (pin "35") (pinfunction "TXD0_35") (pintype "bidirectional"))
    )
    (net (code "63") (name "VDD") (class "Default")
      (node (ref "C3") (pin "1") (pinfunction "1_1") (pintype "passive"))
      (node (ref "D1") (pin "C") (pinfunction "C_C") (pintype "passive"))
      (node (ref "J8") (pin "6") (pinfunction "6_6") (pintype "passive"))
      (node (ref "L1") (pin "P$2") (pinfunction "2_P$2") (pintype "passive"))
      (node (ref "R17") (pin "1") (pinfunction "1_1") (pintype "passive"))
      (node (ref "R21") (pin "2") (pinfunction "2_2") (pintype "passive"))
      (node (ref "R22") (pin "2") (pinfunction "2_2") (pintype "passive"))
      (node (ref "R23") (pin "2") (pinfunction "2_2") (pintype "passive"))
      (node (ref "R28") (pin "2") (pinfunction "2_2") (pintype "passive"))
      (node (ref "R29") (pin "2") (pinfunction "2_2") (pintype "passive"))
      (node (ref "R7") (pin "2") (pinfunction "2_2") (pintype "passive"))
      (node (ref "U$3") (pin "2") (pinfunction "3V3_2") (pintype "bidirectional"))
      (node (ref "U$4") (pin "P$2") (pinfunction "P+_P$2") (pintype "power_in"))
      (node (ref "U2") (pin "8") (pinfunction "VCC_8") (pintype "power_in"))
      (node (ref "U3") (pin "1") (pinfunction "FB/VOUT_1") (pintype "bidirectional"))
      (node (ref "U3") (pin "2") (pinfunction "OUT_2") (pintype "output"))
      (node (ref "U3") (pin "8") (pinfunction "BD_8") (pintype "passive"))
    )
    (net (code "64") (name "WTR-SENS") (class "Default")
      (node (ref "J8") (pin "5") (pinfunction "5_5") (pintype "passive"))
      (node (ref "R2") (pin "1") (pinfunction "1_1") (pintype "passive"))
      (node (ref "R6") (pin "2") (pinfunction "2_2") (pintype "passive"))
    )
    (net (code "65") (name "unconnected-(U$1-AIN2-Pad10)") (class "Default")
      (node (ref "U$1") (pin "10") (pinfunction "AIN2_10") (pintype "bidirectional"))
    )
    (net (code "66") (name "unconnected-(U$1-CELLX-Pad13)") (class "Default")
      (node (ref "U$1") (pin "13") (pinfunction "CELLX_13") (pintype "bidirectional"))
    )
    (net (code "67") (name "unconnected-(U$3-CLK-Pad20)") (class "Default")
      (node (ref "U$3") (pin "20") (pinfunction "CLK_20") (pintype "bidirectional"))
    )
    (net (code "68") (name "unconnected-(U$3-IO02-Pad24)") (class "Default")
      (node (ref "U$3") (pin "24") (pinfunction "IO02_24") (pintype "bidirectional"))
    )
    (net (code "69") (name "unconnected-(U$3-IO04-Pad26)") (class "Default")
      (node (ref "U$3") (pin "26") (pinfunction "IO04_26") (pintype "bidirectional"))
    )
    (net (code "70") (name "unconnected-(U$3-IO09-Pad17)") (class "Default")
      (node (ref "U$3") (pin "17") (pinfunction "IO09_17") (pintype "bidirectional"))
    )
    (net (code "71") (name "unconnected-(U$3-IO10-Pad18)") (class "Default")
      (node (ref "U$3") (pin "18") (pinfunction "IO10_18") (pintype "bidirectional"))
    )
    (net (code "72") (name "unconnected-(U$3-IO12-Pad14)") (class "Default")
      (node (ref "U$3") (pin "14") (pinfunction "IO12_14") (pintype "bidirectional"))
    )
    (net (code "73") (name "unconnected-(U$3-IO13-Pad16)") (class "Default")
      (node (ref "U$3") (pin "16") (pinfunction "IO13_16") (pintype "bidirectional"))
    )
    (net (code "74") (name "unconnected-(U$3-IO14-Pad13)") (class "Default")
      (node (ref "U$3") (pin "13") (pinfunction "IO14_13") (pintype "bidirectional"))
    )
    (net (code "75") (name "unconnected-(U$3-IO15-Pad23)") (class "Default")
      (node (ref "U$3") (pin "23") (pinfunction "IO15_23") (pintype "bidirectional"))
    )
    (net (code "76") (name "unconnected-(U$3-IO16-Pad27)") (class "Default")
      (node (ref "U$3") (pin "27") (pinfunction "IO16_27") (pintype "bidirectional"))
    )
    (net (code "77") (name "unconnected-(U$3-IO17-Pad28)") (class "Default")
      (node (ref "U$3") (pin "28") (pinfunction "IO17_28") (pintype "bidirectional"))
    )
    (net (code "78") (name "unconnected-(U$3-IO23_SPI_MOSI-Pad37)") (class "Default")
      (node (ref "U$3") (pin "37") (pinfunction "IO23_SPI_MOSI_37") (pintype "bidirectional"))
    )
    (net (code "79") (name "unconnected-(U$3-IO32-Pad8)") (class "Default")
      (node (ref "U$3") (pin "8") (pinfunction "IO32_8") (pintype "bidirectional"))
    )
    (net (code "80") (name "unconnected-(U$3-IO33-Pad9)") (class "Default")
      (node (ref "U$3") (pin "9") (pinfunction "IO33_9") (pintype "bidirectional"))
    )
    (net (code "81") (name "unconnected-(U$3-NC-Pad32)") (class "Default")
      (node (ref "U$3") (pin "32") (pinfunction "NC_32") (pintype "bidirectional"))
    )
    (net (code "82") (name "unconnected-(U$3-SD1-Pad22)") (class "Default")
      (node (ref "U$3") (pin "22") (pinfunction "SD1_22") (pintype "bidirectional"))
    )
    (net (code "83") (name "unconnected-(U$3-SD2-Pad19)") (class "Default")
      (node (ref "U$3") (pin "19") (pinfunction "SD2_19") (pintype "bidirectional"))
    )
    (net (code "84") (name "unconnected-(U$3-SD3-Pad21)") (class "Default")
      (node (ref "U$3") (pin "21") (pinfunction "SD3_21") (pintype "bidirectional"))
    )
    (net (code "85") (name "unconnected-(U$6-NC1-Pad8)") (class "Default")
      (node (ref "U$6") (pin "8") (pinfunction "NC1_8") (pintype "bidirectional"))
    )
    (net (code "86") (name "unconnected-(U$6-NC2-Pad9)") (class "Default")
      (node (ref "U$6") (pin "9") (pinfunction "NC2_9") (pintype "bidirectional"))
    )
  )
)
